# 1-Schematic_Seven_Lions.net
KiCad netlist of a schematic drawn in EasyEDA
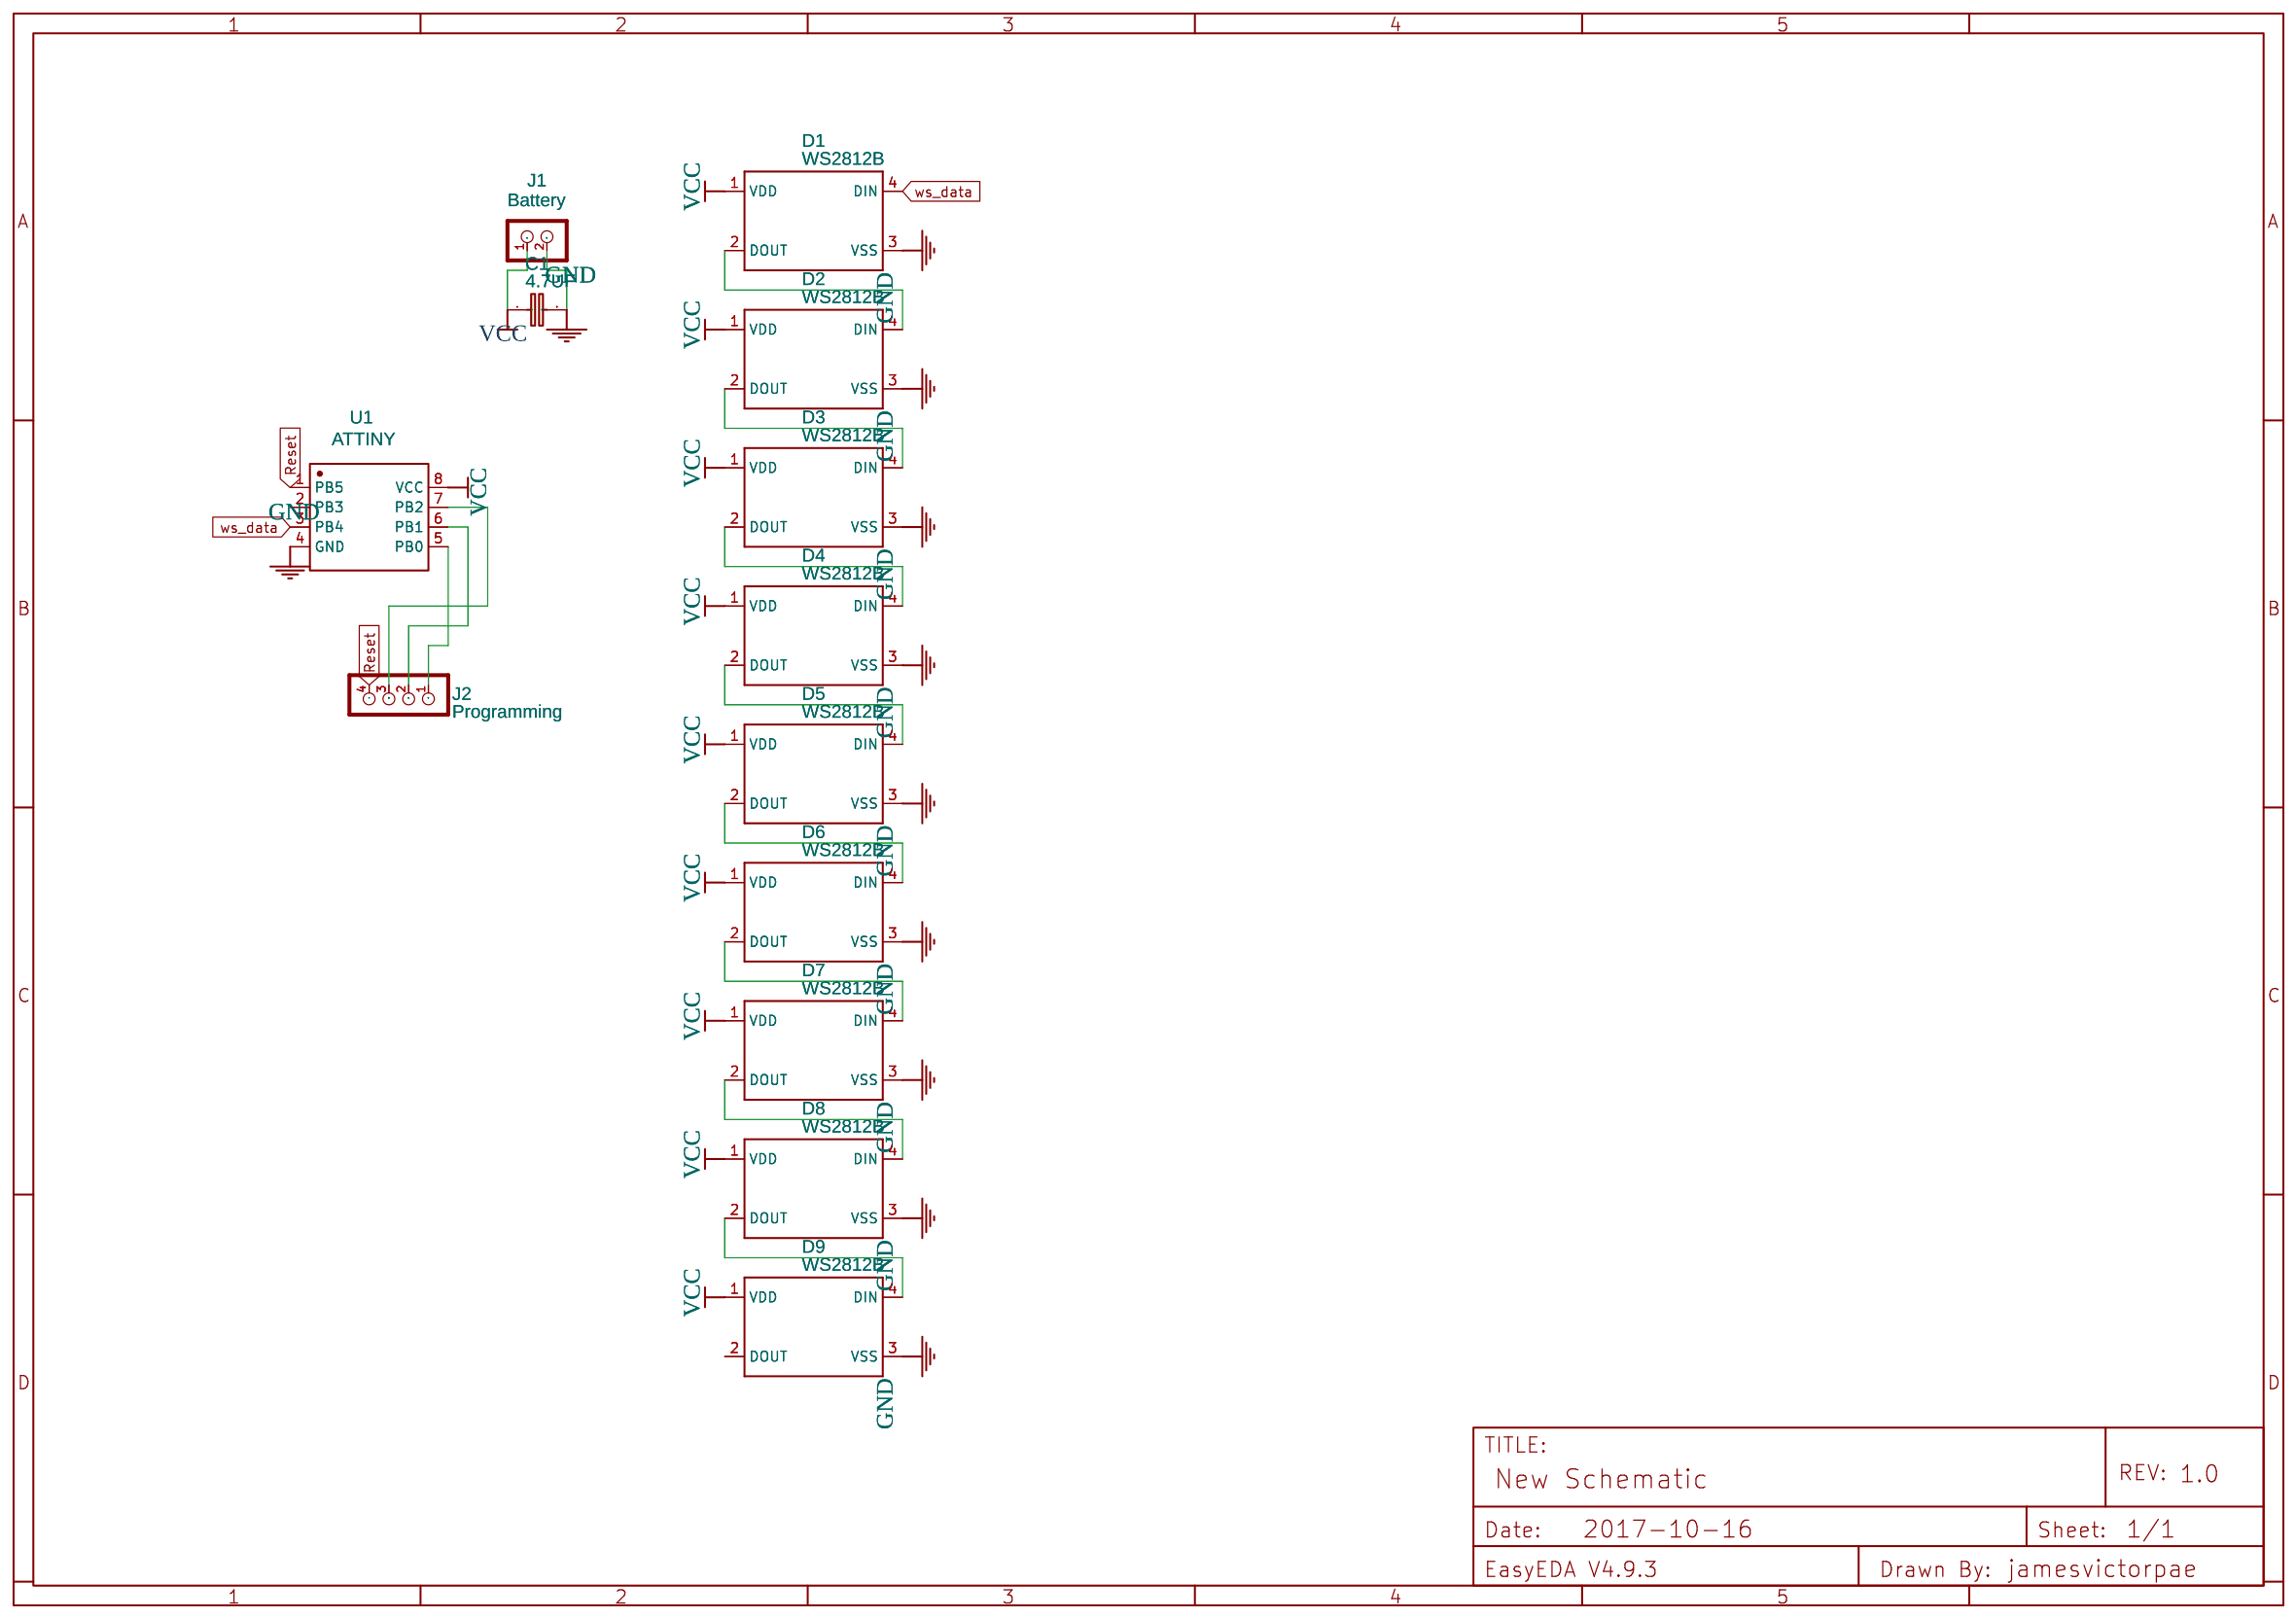
[diagram p0: schematic sheet]

(export (version "E")
  (design (tool "Eeschema 10.0.6"))
  (components
    (comp (ref "C1")
      (value "4.7UF")
      (fields (field (name "BOM_Manufacturer Part") "?"))
      (libsource (lib "") (part "Unknown_270_150"))
    )
    (comp (ref "D1")
      (value "WS2812B")
      (fields (field (name "BOM_Manufacturer Part") "?"))
      (libsource (lib "") (part "Unknown_380_110"))
    )
    (comp (ref "D2")
      (value "WS2812B")
      (fields (field (name "BOM_Manufacturer Part") "?"))
      (libsource (lib "") (part "Unknown_380_180"))
    )
    (comp (ref "D3")
      (value "WS2812B")
      (fields (field (name "BOM_Manufacturer Part") "?"))
      (libsource (lib "") (part "Unknown_380_250"))
    )
    (comp (ref "D4")
      (value "WS2812B")
      (fields (field (name "BOM_Manufacturer Part") "?"))
      (libsource (lib "") (part "Unknown_380_320"))
    )
    (comp (ref "D5")
      (value "WS2812B")
      (fields (field (name "BOM_Manufacturer Part") "?"))
      (libsource (lib "") (part "Unknown_380_390"))
    )
    (comp (ref "D6")
      (value "WS2812B")
      (fields (field (name "BOM_Manufacturer Part") "?"))
      (libsource (lib "") (part "Unknown_380_460"))
    )
    (comp (ref "D7")
      (value "WS2812B")
      (fields (field (name "BOM_Manufacturer Part") "?"))
      (libsource (lib "") (part "Unknown_380_530"))
    )
    (comp (ref "D8")
      (value "WS2812B")
      (fields (field (name "BOM_Manufacturer Part") "?"))
      (libsource (lib "") (part "Unknown_380_600"))
    )
    (comp (ref "D9")
      (value "WS2812B")
      (fields (field (name "BOM_Manufacturer Part") "?"))
      (libsource (lib "") (part "Unknown_380_670"))
    )
    (comp (ref "J1")
      (value "Battery")
      (fields (field (name "BOM_Manufacturer Part") "?"))
      (libsource (lib "") (part "Unknown_260_120"))
    )
    (comp (ref "J2")
      (value "Programming")
      (fields (field (name "BOM_Manufacturer Part") "?"))
      (libsource (lib "") (part "Unknown_200_340"))
    )
    (comp (ref "U1")
      (value "ATTINY")
      (fields (field (name "BOM_Manufacturer Part") "ATTINY85-20SU"))
      (libsource (lib "") (part "Unknown_180_230"))
    )
  )
  (nets
    (net (code "1") (name "GND") (class "Default")
      (node (ref "C1") (pin "2") (pinfunction "2_2") (pintype "unspecified"))
      (node (ref "D1") (pin "3") (pinfunction "VSS_3") (pintype "passive"))
      (node (ref "D2") (pin "3") (pinfunction "VSS_3") (pintype "passive"))
      (node (ref "D3") (pin "3") (pinfunction "VSS_3") (pintype "passive"))
      (node (ref "D4") (pin "3") (pinfunction "VSS_3") (pintype "passive"))
      (node (ref "D5") (pin "3") (pinfunction "VSS_3") (pintype "passive"))
      (node (ref "D6") (pin "3") (pinfunction "VSS_3") (pintype "passive"))
      (node (ref "D7") (pin "3") (pinfunction "VSS_3") (pintype "passive"))
      (node (ref "D8") (pin "3") (pinfunction "VSS_3") (pintype "passive"))
      (node (ref "D9") (pin "3") (pinfunction "VSS_3") (pintype "passive"))
      (node (ref "J1") (pin "2") (pinfunction "2_2") (pintype "unspecified"))
      (node (ref "U1") (pin "4") (pinfunction "GND_4") (pintype "unspecified"))
    )
    (net (code "2") (name "Net-(D1-DOUT)") (class "Default")
      (node (ref "D1") (pin "2") (pinfunction "DOUT_2") (pintype "output"))
      (node (ref "D2") (pin "4") (pinfunction "DIN_4") (pintype "input"))
    )
    (net (code "3") (name "Net-(D2-DOUT)") (class "Default")
      (node (ref "D2") (pin "2") (pinfunction "DOUT_2") (pintype "output"))
      (node (ref "D3") (pin "4") (pinfunction "DIN_4") (pintype "input"))
    )
    (net (code "4") (name "Net-(D3-DOUT)") (class "Default")
      (node (ref "D3") (pin "2") (pinfunction "DOUT_2") (pintype "output"))
      (node (ref "D4") (pin "4") (pinfunction "DIN_4") (pintype "input"))
    )
    (net (code "5") (name "Net-(D4-DOUT)") (class "Default")
      (node (ref "D4") (pin "2") (pinfunction "DOUT_2") (pintype "output"))
      (node (ref "D5") (pin "4") (pinfunction "DIN_4") (pintype "input"))
    )
    (net (code "6") (name "Net-(D5-DOUT)") (class "Default")
      (node (ref "D5") (pin "2") (pinfunction "DOUT_2") (pintype "output"))
      (node (ref "D6") (pin "4") (pinfunction "DIN_4") (pintype "input"))
    )
    (net (code "7") (name "Net-(D6-DOUT)") (class "Default")
      (node (ref "D6") (pin "2") (pinfunction "DOUT_2") (pintype "output"))
      (node (ref "D7") (pin "4") (pinfunction "DIN_4") (pintype "input"))
    )
    (net (code "8") (name "Net-(D7-DOUT)") (class "Default")
      (node (ref "D7") (pin "2") (pinfunction "DOUT_2") (pintype "output"))
      (node (ref "D8") (pin "4") (pinfunction "DIN_4") (pintype "input"))
    )
    (net (code "9") (name "Net-(D8-DOUT)") (class "Default")
      (node (ref "D8") (pin "2") (pinfunction "DOUT_2") (pintype "output"))
      (node (ref "D9") (pin "4") (pinfunction "DIN_4") (pintype "input"))
    )
    (net (code "10") (name "Net-(U1-PB0)") (class "Default")
      (node (ref "J2") (pin "1") (pinfunction "1_1") (pintype "unspecified"))
      (node (ref "U1") (pin "5") (pinfunction "PB0_5") (pintype "unspecified"))
    )
    (net (code "11") (name "Net-(U1-PB1)") (class "Default")
      (node (ref "J2") (pin "2") (pinfunction "2_2") (pintype "unspecified"))
      (node (ref "U1") (pin "6") (pinfunction "PB1_6") (pintype "unspecified"))
    )
    (net (code "12") (name "Net-(U1-PB2)") (class "Default")
      (node (ref "J2") (pin "3") (pinfunction "3_3") (pintype "unspecified"))
      (node (ref "U1") (pin "7") (pinfunction "PB2_7") (pintype "unspecified"))
    )
    (net (code "13") (name "Reset") (class "Default")
      (node (ref "J2") (pin "4") (pinfunction "4_4") (pintype "unspecified"))
      (node (ref "U1") (pin "1") (pinfunction "PB5_1") (pintype "unspecified"))
    )
    (net (code "14") (name "VCC") (class "Default")
      (node (ref "C1") (pin "1") (pinfunction "1_1") (pintype "unspecified"))
      (node (ref "D1") (pin "1") (pinfunction "VDD_1") (pintype "passive"))
      (node (ref "D2") (pin "1") (pinfunction "VDD_1") (pintype "passive"))
      (node (ref "D3") (pin "1") (pinfunction "VDD_1") (pintype "passive"))
      (node (ref "D4") (pin "1") (pinfunction "VDD_1") (pintype "passive"))
      (node (ref "D5") (pin "1") (pinfunction "VDD_1") (pintype "passive"))
      (node (ref "D6") (pin "1") (pinfunction "VDD_1") (pintype "passive"))
      (node (ref "D7") (pin "1") (pinfunction "VDD_1") (pintype "passive"))
      (node (ref "D8") (pin "1") (pinfunction "VDD_1") (pintype "passive"))
      (node (ref "D9") (pin "1") (pinfunction "VDD_1") (pintype "passive"))
      (node (ref "J1") (pin "1") (pinfunction "1_1") (pintype "unspecified"))
      (node (ref "U1") (pin "8") (pinfunction "VCC_8") (pintype "unspecified"))
    )
    (net (code "15") (name "unconnected-(D9-DOUT-Pad2)") (class "Default")
      (node (ref "D9") (pin "2") (pinfunction "DOUT_2") (pintype "output"))
    )
    (net (code "16") (name "unconnected-(U1-PB3-Pad2)") (class "Default")
      (node (ref "U1") (pin "2") (pinfunction "PB3_2") (pintype "unspecified"))
    )
    (net (code "17") (name "ws_data") (class "Default")
      (node (ref "D1") (pin "4") (pinfunction "DIN_4") (pintype "input"))
      (node (ref "U1") (pin "3") (pinfunction "PB4_3") (pintype "unspecified"))
    )
  )
)
